# board.net
KiCad netlist of a schematic drawn in EAGLE
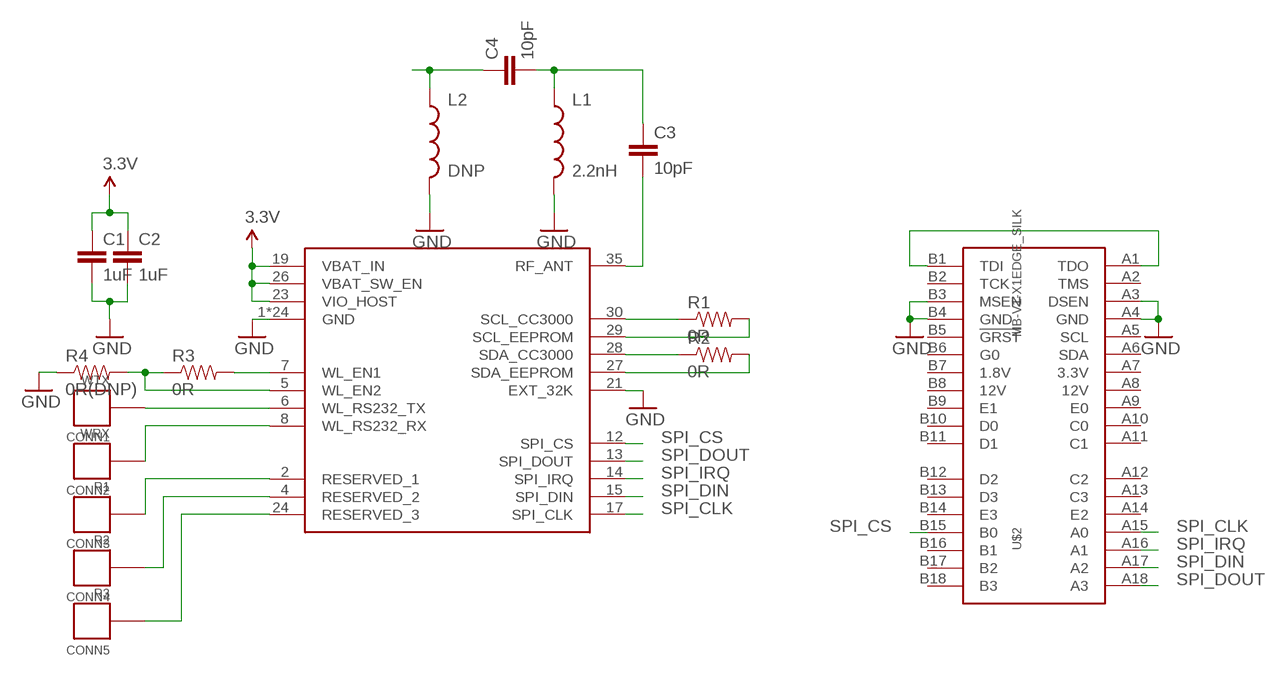
[diagram p0: schematic, sheet 1]

(export (version "E")
  (design (tool "Eeschema 10.0.6"))
  (components
    (comp (ref "C1")
      (value "1uF")
      (footprint "eagle-import:0603-CAP")
      (libsource (lib "eagle-import") (part "CAP0603"))
    )
    (comp (ref "C2")
      (value "1uF")
      (footprint "eagle-import:0603-CAP")
      (libsource (lib "eagle-import") (part "CAP0603"))
    )
    (comp (ref "C3")
      (value "10pF")
      (footprint "eagle-import:0402-CAP")
      (libsource (lib "eagle-import") (part "CAP0402-CAP"))
    )
    (comp (ref "C4")
      (value "10pF")
      (footprint "eagle-import:0402-CAP")
      (libsource (lib "eagle-import") (part "CAP0402-CAP"))
    )
    (comp (ref "CONN1")
      (value "WTX")
      (footprint "eagle-import:HOLE_22AWG")
      (libsource (lib "eagle-import") (part "CONNECTOR22AWG"))
    )
    (comp (ref "CONN2")
      (value "WRX")
      (footprint "eagle-import:HOLE_22AWG")
      (libsource (lib "eagle-import") (part "CONNECTOR22AWG"))
    )
    (comp (ref "CONN3")
      (value "R1")
      (footprint "eagle-import:HOLE_22AWG")
      (libsource (lib "eagle-import") (part "CONNECTOR22AWG"))
    )
    (comp (ref "CONN4")
      (value "R2")
      (footprint "eagle-import:HOLE_22AWG")
      (libsource (lib "eagle-import") (part "CONNECTOR22AWG"))
    )
    (comp (ref "CONN5")
      (value "R3")
      (footprint "eagle-import:HOLE_22AWG")
      (libsource (lib "eagle-import") (part "CONNECTOR22AWG"))
    )
    (comp (ref "L1")
      (value "2.2nH")
      (footprint "eagle-import:0603")
      (libsource (lib "eagle-import") (part "INDUCTOR0603"))
    )
    (comp (ref "L2")
      (value "DNP")
      (footprint "eagle-import:0603")
      (libsource (lib "eagle-import") (part "INDUCTOR0603"))
    )
    (comp (ref "R1")
      (value "0R")
      (footprint "eagle-import:0603-RES")
      (libsource (lib "eagle-import") (part "RESISTOR0603"))
    )
    (comp (ref "R2")
      (value "0R")
      (footprint "eagle-import:0603-RES")
      (libsource (lib "eagle-import") (part "RESISTOR0603"))
    )
    (comp (ref "R3")
      (value "0R")
      (footprint "eagle-import:0603-RES")
      (libsource (lib "eagle-import") (part "RESISTOR0603"))
    )
    (comp (ref "R4")
      (value "0R(DNP)")
      (footprint "eagle-import:0603-RES")
      (libsource (lib "eagle-import") (part "RESISTOR0603"))
    )
    (comp (ref "U$1")
      (value "CC3000")
      (footprint "eagle-import:CC3000")
      (libsource (lib "eagle-import") (part "CC3000"))
    )
    (comp (ref "U$2")
      (value "MB-V1-X1EDGE_SILK")
      (footprint "eagle-import:MB-V1-X1-EDGE")
      (libsource (lib "eagle-import") (part "MB-V1-X1EDGE_SILK"))
    )
  )
  (nets
    (net (code "1") (name "/SPI_CLK") (class "Default")
      (node (ref "U$1") (pin "17") (pinfunction "SPI_CLK_17") (pintype "bidirectional"))
      (node (ref "U$2") (pin "A15") (pinfunction "A0_A15") (pintype "bidirectional"))
    )
    (net (code "2") (name "/SPI_CS") (class "Default")
      (node (ref "U$1") (pin "12") (pinfunction "SPI_CS_12") (pintype "bidirectional"))
      (node (ref "U$2") (pin "B15") (pinfunction "B0_B15") (pintype "bidirectional"))
    )
    (net (code "3") (name "/SPI_DIN") (class "Default")
      (node (ref "U$1") (pin "15") (pinfunction "SPI_DIN_15") (pintype "bidirectional"))
      (node (ref "U$2") (pin "A17") (pinfunction "A2_A17") (pintype "bidirectional"))
    )
    (net (code "4") (name "/SPI_DOUT") (class "Default")
      (node (ref "U$1") (pin "13") (pinfunction "SPI_DOUT_13") (pintype "bidirectional"))
      (node (ref "U$2") (pin "A18") (pinfunction "A3_A18") (pintype "bidirectional"))
    )
    (net (code "5") (name "/SPI_IRQ") (class "Default")
      (node (ref "U$1") (pin "14") (pinfunction "SPI_IRQ_14") (pintype "bidirectional"))
      (node (ref "U$2") (pin "A16") (pinfunction "A1_A16") (pintype "bidirectional"))
    )
    (net (code "6") (name "3.3V") (class "Default")
      (node (ref "C1") (pin "1") (pinfunction "1_1") (pintype "passive"))
      (node (ref "C2") (pin "1") (pinfunction "1_1") (pintype "passive"))
      (node (ref "U$1") (pin "19") (pinfunction "VBAT_IN_19") (pintype "bidirectional"))
      (node (ref "U$1") (pin "23") (pinfunction "VIO_HOST_23") (pintype "bidirectional"))
      (node (ref "U$1") (pin "26") (pinfunction "VBAT_SW_EN_26") (pintype "bidirectional"))
    )
    (net (code "7") (name "GND") (class "Default")
      (node (ref "C1") (pin "2") (pinfunction "2_2") (pintype "passive"))
      (node (ref "C2") (pin "2") (pinfunction "2_2") (pintype "passive"))
      (node (ref "L1") (pin "2") (pinfunction "2_2") (pintype "passive"))
      (node (ref "L2") (pin "2") (pinfunction "2_2") (pintype "passive"))
      (node (ref "R4") (pin "1") (pinfunction "1_1") (pintype "passive"))
      (node (ref "U$1") (pin "1") (pinfunction "GND_1") (pintype "bidirectional"))
      (node (ref "U$1") (pin "10") (pinfunction "GND_10") (pintype "bidirectional"))
      (node (ref "U$1") (pin "11") (pinfunction "GND_11") (pintype "bidirectional"))
      (node (ref "U$1") (pin "16") (pinfunction "GND_16") (pintype "bidirectional"))
      (node (ref "U$1") (pin "18") (pinfunction "GND_18") (pintype "bidirectional"))
      (node (ref "U$1") (pin "20") (pinfunction "GND_20") (pintype "bidirectional"))
      (node (ref "U$1") (pin "21") (pinfunction "EXT_32K_21") (pintype "bidirectional"))
      (node (ref "U$1") (pin "22") (pinfunction "GND_22") (pintype "bidirectional"))
      (node (ref "U$1") (pin "25") (pinfunction "GND_25") (pintype "bidirectional"))
      (node (ref "U$1") (pin "31") (pinfunction "GND_31") (pintype "bidirectional"))
      (node (ref "U$1") (pin "32") (pinfunction "GND_32") (pintype "bidirectional"))
      (node (ref "U$1") (pin "33") (pinfunction "GND_33") (pintype "bidirectional"))
      (node (ref "U$1") (pin "34") (pinfunction "GND_34") (pintype "bidirectional"))
      (node (ref "U$1") (pin "36") (pinfunction "GND_36") (pintype "bidirectional"))
      (node (ref "U$1") (pin "37") (pinfunction "GND_37") (pintype "bidirectional"))
      (node (ref "U$1") (pin "38") (pinfunction "GND_38") (pintype "bidirectional"))
      (node (ref "U$1") (pin "39") (pinfunction "GND_39") (pintype "bidirectional"))
      (node (ref "U$1") (pin "40") (pinfunction "GND_40") (pintype "bidirectional"))
      (node (ref "U$1") (pin "41") (pinfunction "GND_41") (pintype "bidirectional"))
      (node (ref "U$1") (pin "42") (pinfunction "GND_42") (pintype "bidirectional"))
      (node (ref "U$1") (pin "43") (pinfunction "GND_43") (pintype "bidirectional"))
      (node (ref "U$1") (pin "44") (pinfunction "GND_44") (pintype "bidirectional"))
      (node (ref "U$1") (pin "45") (pinfunction "GND_45") (pintype "bidirectional"))
      (node (ref "U$1") (pin "46") (pinfunction "GND_46") (pintype "bidirectional"))
      (node (ref "U$1") (pin "9") (pinfunction "GND_9") (pintype "bidirectional"))
      (node (ref "U$2") (pin "A3") (pinfunction "DSEN_A3") (pintype "bidirectional"))
      (node (ref "U$2") (pin "A4") (pinfunction "GND_A4") (pintype "input"))
      (node (ref "U$2") (pin "B3") (pinfunction "MSEN_B3") (pintype "bidirectional"))
      (node (ref "U$2") (pin "B4") (pinfunction "GND_B4") (pintype "input"))
    )
    (net (code "8") (name "Net-(C3-Pad1)") (class "Default")
      (node (ref "C3") (pin "1") (pinfunction "1_1") (pintype "passive"))
      (node (ref "C4") (pin "2") (pinfunction "2_2") (pintype "passive"))
      (node (ref "L1") (pin "1") (pinfunction "1_1") (pintype "passive"))
    )
    (net (code "9") (name "Net-(C4-Pad1)") (class "Default")
      (node (ref "C4") (pin "1") (pinfunction "1_1") (pintype "passive"))
      (node (ref "L2") (pin "1") (pinfunction "1_1") (pintype "passive"))
    )
    (net (code "10") (name "Net-(U$1-RESERVED_1)") (class "Default")
      (node (ref "CONN3") (pin "P") (pinfunction "P_P") (pintype "bidirectional"))
      (node (ref "U$1") (pin "2") (pinfunction "RESERVED_1_2") (pintype "bidirectional"))
    )
    (net (code "11") (name "Net-(U$1-RESERVED_2)") (class "Default")
      (node (ref "CONN4") (pin "P") (pinfunction "P_P") (pintype "bidirectional"))
      (node (ref "U$1") (pin "4") (pinfunction "RESERVED_2_4") (pintype "bidirectional"))
    )
    (net (code "12") (name "Net-(U$1-RESERVED_3)") (class "Default")
      (node (ref "CONN5") (pin "P") (pinfunction "P_P") (pintype "bidirectional"))
      (node (ref "U$1") (pin "24") (pinfunction "RESERVED_3_24") (pintype "bidirectional"))
    )
    (net (code "13") (name "Net-(U$1-RF_ANT)") (class "Default")
      (node (ref "C3") (pin "2") (pinfunction "2_2") (pintype "passive"))
      (node (ref "U$1") (pin "35") (pinfunction "RF_ANT_35") (pintype "bidirectional"))
    )
    (net (code "14") (name "Net-(U$1-SCL_CC3000)") (class "Default")
      (node (ref "R1") (pin "1") (pinfunction "1_1") (pintype "passive"))
      (node (ref "U$1") (pin "30") (pinfunction "SCL_CC3000_30") (pintype "bidirectional"))
    )
    (net (code "15") (name "Net-(U$1-SCL_EEPROM)") (class "Default")
      (node (ref "R1") (pin "2") (pinfunction "2_2") (pintype "passive"))
      (node (ref "U$1") (pin "29") (pinfunction "SCL_EEPROM_29") (pintype "bidirectional"))
    )
    (net (code "16") (name "Net-(U$1-SDA_CC3000)") (class "Default")
      (node (ref "R2") (pin "1") (pinfunction "1_1") (pintype "passive"))
      (node (ref "U$1") (pin "28") (pinfunction "SDA_CC3000_28") (pintype "bidirectional"))
    )
    (net (code "17") (name "Net-(U$1-SDA_EEPROM)") (class "Default")
      (node (ref "R2") (pin "2") (pinfunction "2_2") (pintype "passive"))
      (node (ref "U$1") (pin "27") (pinfunction "SDA_EEPROM_27") (pintype "bidirectional"))
    )
    (net (code "18") (name "Net-(U$1-WL_EN1)") (class "Default")
      (node (ref "R3") (pin "2") (pinfunction "2_2") (pintype "passive"))
      (node (ref "U$1") (pin "7") (pinfunction "WL_EN1_7") (pintype "bidirectional"))
    )
    (net (code "19") (name "Net-(U$1-WL_EN2)") (class "Default")
      (node (ref "R3") (pin "1") (pinfunction "1_1") (pintype "passive"))
      (node (ref "R4") (pin "2") (pinfunction "2_2") (pintype "passive"))
      (node (ref "U$1") (pin "5") (pinfunction "WL_EN2_5") (pintype "bidirectional"))
    )
    (net (code "20") (name "Net-(U$1-WL_RS232_RX)") (class "Default")
      (node (ref "CONN2") (pin "P") (pinfunction "P_P") (pintype "bidirectional"))
      (node (ref "U$1") (pin "8") (pinfunction "WL_RS232_RX_8") (pintype "bidirectional"))
    )
    (net (code "21") (name "Net-(U$1-WL_RS232_TX)") (class "Default")
      (node (ref "CONN1") (pin "P") (pinfunction "P_P") (pintype "bidirectional"))
      (node (ref "U$1") (pin "6") (pinfunction "WL_RS232_TX_6") (pintype "bidirectional"))
    )
    (net (code "22") (name "Net-(U$2-TDI)") (class "Default")
      (node (ref "U$2") (pin "A1") (pinfunction "TDO_A1") (pintype "bidirectional"))
      (node (ref "U$2") (pin "B1") (pinfunction "TDI_B1") (pintype "input"))
    )
    (net (code "23") (name "unconnected-(U$2-1.8V-PadB7)") (class "Default")
      (node (ref "U$2") (pin "B7") (pinfunction "1.8V_B7") (pintype "bidirectional"))
    )
    (net (code "24") (name "unconnected-(U$2-3.3V-PadA7)") (class "Default")
      (node (ref "U$2") (pin "A7") (pinfunction "3.3V_A7") (pintype "bidirectional"))
    )
    (net (code "25") (name "unconnected-(U$2-12V-PadA8)") (class "Default")
      (node (ref "U$2") (pin "A8") (pinfunction "12V_A8") (pintype "bidirectional"))
    )
    (net (code "26") (name "unconnected-(U$2-12V-PadB8)") (class "Default")
      (node (ref "U$2") (pin "B8") (pinfunction "12V_B8") (pintype "bidirectional"))
    )
    (net (code "27") (name "unconnected-(U$2-B1-PadB16)") (class "Default")
      (node (ref "U$2") (pin "B16") (pinfunction "B1_B16") (pintype "bidirectional"))
    )
    (net (code "28") (name "unconnected-(U$2-B2-PadB17)") (class "Default")
      (node (ref "U$2") (pin "B17") (pinfunction "B2_B17") (pintype "bidirectional"))
    )
    (net (code "29") (name "unconnected-(U$2-B3-PadB18)") (class "Default")
      (node (ref "U$2") (pin "B18") (pinfunction "B3_B18") (pintype "bidirectional"))
    )
    (net (code "30") (name "unconnected-(U$2-C0-PadA10)") (class "Default")
      (node (ref "U$2") (pin "A10") (pinfunction "C0_A10") (pintype "bidirectional"))
    )
    (net (code "31") (name "unconnected-(U$2-C1-PadA11)") (class "Default")
      (node (ref "U$2") (pin "A11") (pinfunction "C1_A11") (pintype "bidirectional"))
    )
    (net (code "32") (name "unconnected-(U$2-C2-PadA12)") (class "Default")
      (node (ref "U$2") (pin "A12") (pinfunction "C2_A12") (pintype "bidirectional"))
    )
    (net (code "33") (name "unconnected-(U$2-C3-PadA13)") (class "Default")
      (node (ref "U$2") (pin "A13") (pinfunction "C3_A13") (pintype "bidirectional"))
    )
    (net (code "34") (name "unconnected-(U$2-D0-PadB10)") (class "Default")
      (node (ref "U$2") (pin "B10") (pinfunction "D0_B10") (pintype "bidirectional"))
    )
    (net (code "35") (name "unconnected-(U$2-D1-PadB11)") (class "Default")
      (node (ref "U$2") (pin "B11") (pinfunction "D1_B11") (pintype "bidirectional"))
    )
    (net (code "36") (name "unconnected-(U$2-D2-PadB12)") (class "Default")
      (node (ref "U$2") (pin "B12") (pinfunction "D2_B12") (pintype "bidirectional"))
    )
    (net (code "37") (name "unconnected-(U$2-D3-PadB13)") (class "Default")
      (node (ref "U$2") (pin "B13") (pinfunction "D3_B13") (pintype "bidirectional"))
    )
    (net (code "38") (name "unconnected-(U$2-E0-PadA9)") (class "Default")
      (node (ref "U$2") (pin "A9") (pinfunction "E0_A9") (pintype "bidirectional"))
    )
    (net (code "39") (name "unconnected-(U$2-E1-PadB9)") (class "Default")
      (node (ref "U$2") (pin "B9") (pinfunction "E1_B9") (pintype "bidirectional"))
    )
    (net (code "40") (name "unconnected-(U$2-E2-PadA14)") (class "Default")
      (node (ref "U$2") (pin "A14") (pinfunction "E2_A14") (pintype "bidirectional"))
    )
    (net (code "41") (name "unconnected-(U$2-E3-PadB14)") (class "Default")
      (node (ref "U$2") (pin "B14") (pinfunction "E3_B14") (pintype "bidirectional"))
    )
    (net (code "42") (name "unconnected-(U$2-G0-PadB6)") (class "Default")
      (node (ref "U$2") (pin "B6") (pinfunction "G0_B6") (pintype "bidirectional"))
    )
    (net (code "43") (name "unconnected-(U$2-SCL-PadA5)") (class "Default")
      (node (ref "U$2") (pin "A5") (pinfunction "SCL_A5") (pintype "bidirectional"))
    )
    (net (code "44") (name "unconnected-(U$2-SDA-PadA6)") (class "Default")
      (node (ref "U$2") (pin "A6") (pinfunction "SDA_A6") (pintype "bidirectional"))
    )
    (net (code "45") (name "unconnected-(U$2-TCK-PadB2)") (class "Default")
      (node (ref "U$2") (pin "B2") (pinfunction "TCK_B2") (pintype "bidirectional"))
    )
    (net (code "46") (name "unconnected-(U$2-TMS-PadA2)") (class "Default")
      (node (ref "U$2") (pin "A2") (pinfunction "TMS_A2") (pintype "bidirectional"))
    )
    (net (code "47") (name "unconnected-(U$2-~{GRST}-PadB5)") (class "Default")
      (node (ref "U$2") (pin "B5") (pinfunction "~{GRST}_B5") (pintype "bidirectional"))
    )
  )
)
